# TramontanaPico.net
KiCad netlist of a schematic drawn in EAGLE
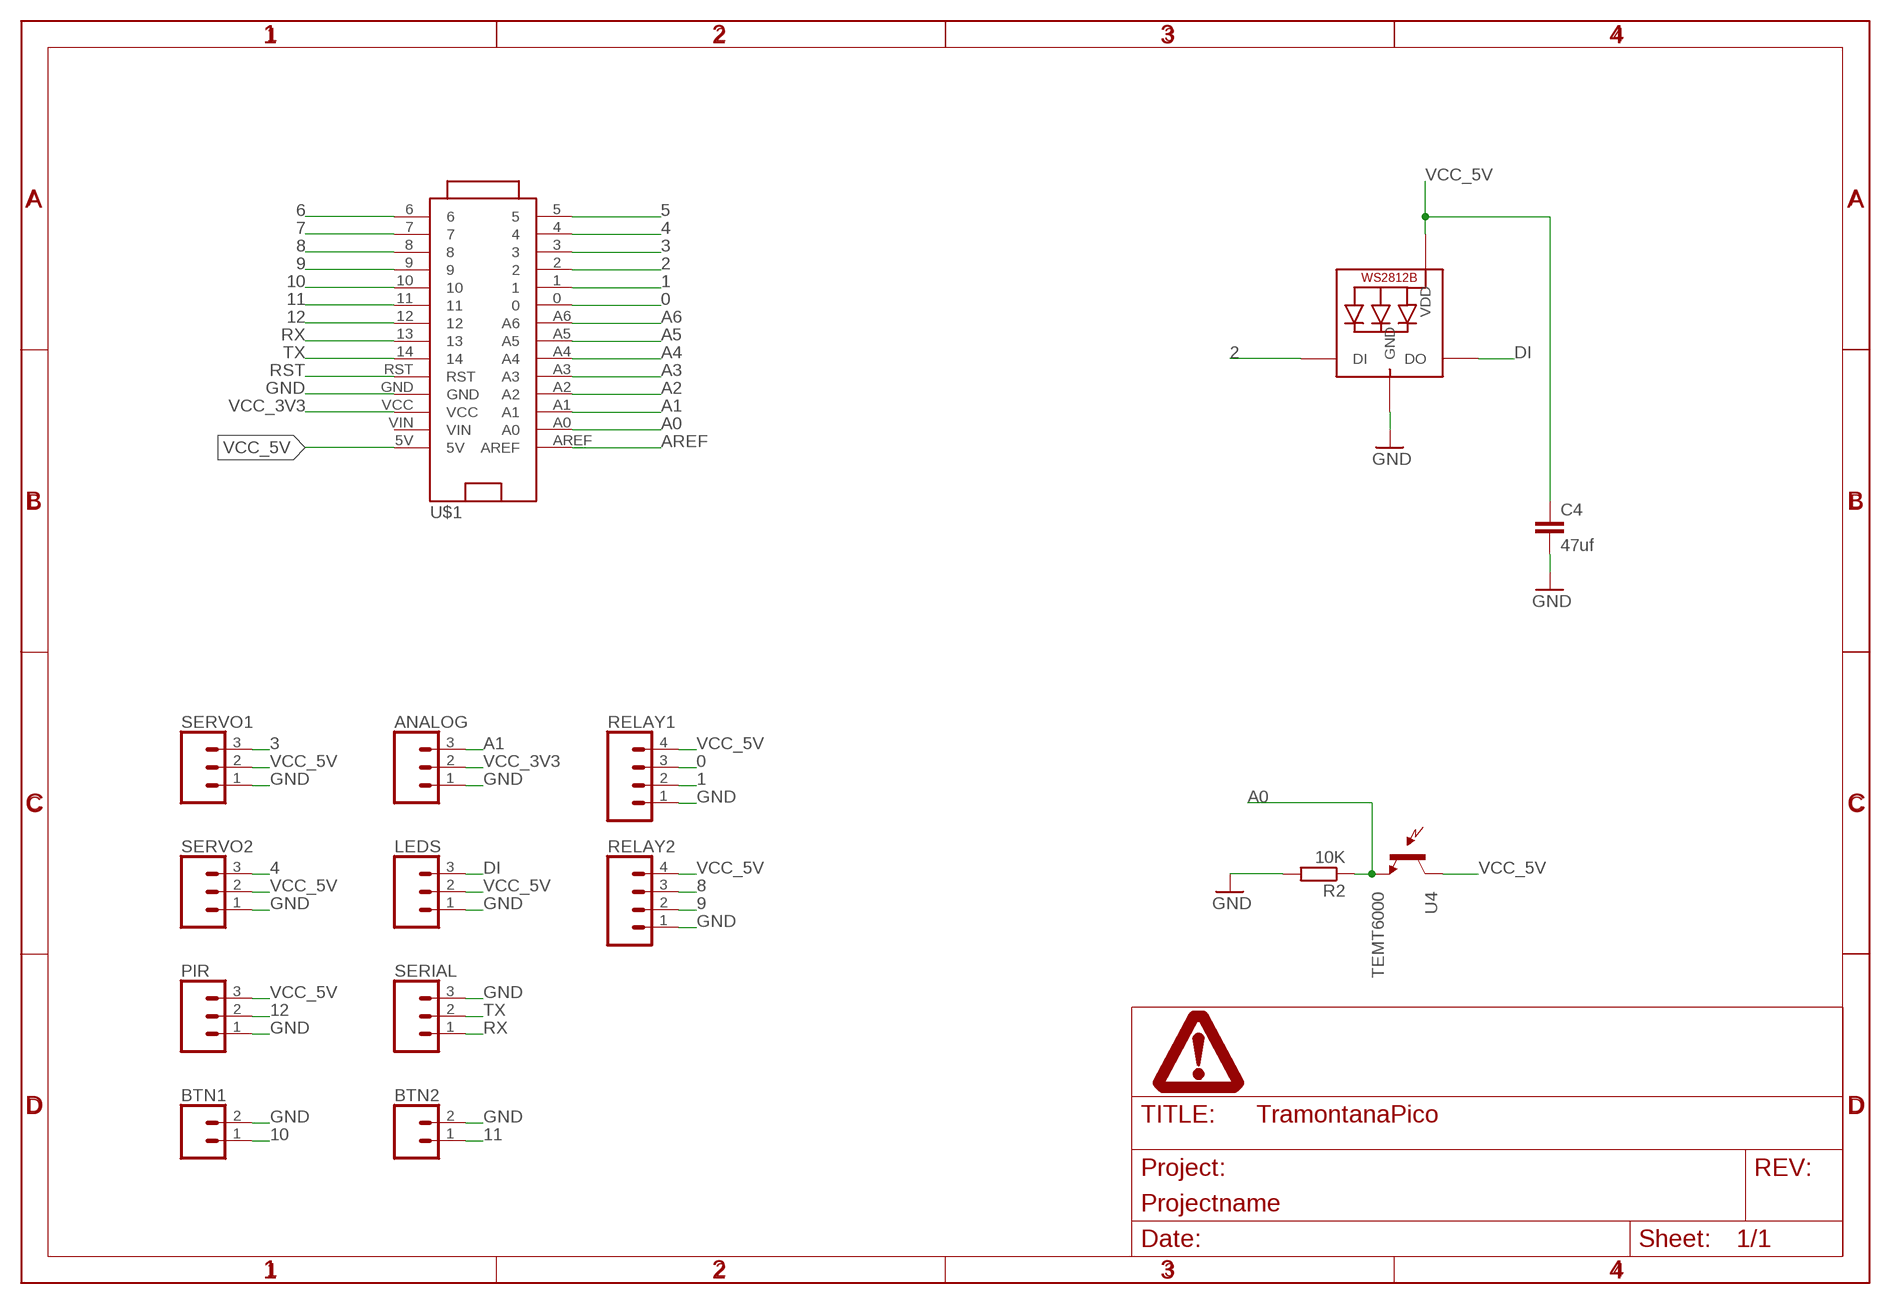
[diagram p0: schematic, sheet 1]

(export (version "E")
  (design (tool "Eeschema 10.0.6"))
  (components
    (comp (ref "ANALOG")
      (value "CONN_03LOCK")
      (footprint "eagle-import:1X03_LOCK")
      (libsource (lib "eagle-import") (part "CONN_03LOCK"))
    )
    (comp (ref "BTN1")
      (value "CONN_02LOCK")
      (footprint "eagle-import:1X02_LOCK")
      (libsource (lib "eagle-import") (part "CONN_02LOCK"))
    )
    (comp (ref "BTN2")
      (value "CONN_02LOCK")
      (footprint "eagle-import:1X02_LOCK")
      (libsource (lib "eagle-import") (part "CONN_02LOCK"))
    )
    (comp (ref "C4")
      (value "47uf")
      (footprint "eagle-import:C0603")
      (libsource (lib "eagle-import") (part "C-EUC0603"))
    )
    (comp (ref "HTTP")
      (value "FRAME_DINA4_L")
      (footprint "eagle-import:DP_LOGO")
      (fields (field (name "PROJECT") "Projectname"))
      (libsource (lib "eagle-import") (part "FRAME_DINA4_L"))
    )
    (comp (ref "LED1")
      (value "WS2812B5050")
      (footprint "eagle-import:WS2812B")
      (libsource (lib "eagle-import") (part "WS2812B5050"))
    )
    (comp (ref "LEDS")
      (value "CONN_03LOCK")
      (footprint "eagle-import:1X03_LOCK")
      (libsource (lib "eagle-import") (part "CONN_03LOCK"))
    )
    (comp (ref "PIR")
      (value "CONN_03LOCK")
      (footprint "eagle-import:1X03_LOCK")
      (libsource (lib "eagle-import") (part "CONN_03LOCK"))
    )
    (comp (ref "R2")
      (value "10K")
      (footprint "eagle-import:R0603")
      (libsource (lib "eagle-import") (part "R-EU_R0603"))
    )
    (comp (ref "RELAY1")
      (value "CONN_04LOCK")
      (footprint "eagle-import:1X04_LOCK")
      (libsource (lib "eagle-import") (part "CONN_04LOCK"))
    )
    (comp (ref "RELAY2")
      (value "CONN_04LOCK")
      (footprint "eagle-import:1X04_LOCK")
      (libsource (lib "eagle-import") (part "CONN_04LOCK"))
    )
    (comp (ref "SERIAL")
      (value "CONN_03LOCK")
      (footprint "eagle-import:1X03_LOCK")
      (libsource (lib "eagle-import") (part "CONN_03LOCK"))
    )
    (comp (ref "SERVO1")
      (value "CONN_03LOCK")
      (footprint "eagle-import:1X03_LOCK")
      (libsource (lib "eagle-import") (part "CONN_03LOCK"))
    )
    (comp (ref "SERVO2")
      (value "CONN_03LOCK")
      (footprint "eagle-import:1X03_LOCK")
      (libsource (lib "eagle-import") (part "CONN_03LOCK"))
    )
    (comp (ref "U$1")
      (value "MKR1000")
      (footprint "eagle-import:MKR1000")
      (libsource (lib "eagle-import") (part "MKR1000"))
    )
    (comp (ref "U4")
      (value "TEMT6000")
      (footprint "eagle-import:TEMT6000-SEN")
      (libsource (lib "eagle-import") (part "TEMT6000"))
    )
  )
  (nets
    (net (code "1") (name "/0") (class "Default")
      (node (ref "RELAY1") (pin "3") (pinfunction "3_3") (pintype "passive"))
      (node (ref "U$1") (pin "0") (pinfunction "0_0") (pintype "bidirectional"))
    )
    (net (code "2") (name "/1") (class "Default")
      (node (ref "RELAY1") (pin "2") (pinfunction "2_2") (pintype "passive"))
      (node (ref "U$1") (pin "1") (pinfunction "1_1") (pintype "bidirectional"))
    )
    (net (code "3") (name "/2") (class "Default")
      (node (ref "LED1") (pin "4-DIN") (pinfunction "DI_4-DIN") (pintype "input"))
      (node (ref "U$1") (pin "2") (pinfunction "2_2") (pintype "bidirectional"))
    )
    (net (code "4") (name "/3") (class "Default")
      (node (ref "SERVO1") (pin "3") (pinfunction "3_3") (pintype "passive"))
      (node (ref "U$1") (pin "3") (pinfunction "3_3") (pintype "bidirectional"))
    )
    (net (code "5") (name "/4") (class "Default")
      (node (ref "SERVO2") (pin "3") (pinfunction "3_3") (pintype "passive"))
      (node (ref "U$1") (pin "4") (pinfunction "4_4") (pintype "bidirectional"))
    )
    (net (code "6") (name "/5") (class "Default")
      (node (ref "U$1") (pin "5") (pinfunction "5_5") (pintype "bidirectional"))
    )
    (net (code "7") (name "/6") (class "Default")
      (node (ref "U$1") (pin "6") (pinfunction "6_6") (pintype "bidirectional"))
    )
    (net (code "8") (name "/7") (class "Default")
      (node (ref "U$1") (pin "7") (pinfunction "7_7") (pintype "bidirectional"))
    )
    (net (code "9") (name "/8") (class "Default")
      (node (ref "RELAY2") (pin "3") (pinfunction "3_3") (pintype "passive"))
      (node (ref "U$1") (pin "8") (pinfunction "8_8") (pintype "bidirectional"))
    )
    (net (code "10") (name "/9") (class "Default")
      (node (ref "RELAY2") (pin "2") (pinfunction "2_2") (pintype "passive"))
      (node (ref "U$1") (pin "9") (pinfunction "9_9") (pintype "bidirectional"))
    )
    (net (code "11") (name "/10") (class "Default")
      (node (ref "BTN1") (pin "1") (pinfunction "1_1") (pintype "passive"))
      (node (ref "U$1") (pin "10") (pinfunction "10_10") (pintype "bidirectional"))
    )
    (net (code "12") (name "/11") (class "Default")
      (node (ref "BTN2") (pin "1") (pinfunction "1_1") (pintype "passive"))
      (node (ref "U$1") (pin "11") (pinfunction "11_11") (pintype "bidirectional"))
    )
    (net (code "13") (name "/12") (class "Default")
      (node (ref "PIR") (pin "2") (pinfunction "2_2") (pintype "passive"))
      (node (ref "U$1") (pin "12") (pinfunction "12_12") (pintype "bidirectional"))
    )
    (net (code "14") (name "/A0") (class "Default")
      (node (ref "R2") (pin "1") (pinfunction "1_1") (pintype "passive"))
      (node (ref "U$1") (pin "A0") (pinfunction "A0_A0") (pintype "bidirectional"))
      (node (ref "U4") (pin "EMITTER") (pinfunction "E1_EMITTER") (pintype "passive"))
    )
    (net (code "15") (name "/A1") (class "Default")
      (node (ref "ANALOG") (pin "3") (pinfunction "3_3") (pintype "passive"))
      (node (ref "U$1") (pin "A1") (pinfunction "A1_A1") (pintype "bidirectional"))
    )
    (net (code "16") (name "/A2") (class "Default")
      (node (ref "U$1") (pin "A2") (pinfunction "A2_A2") (pintype "bidirectional"))
    )
    (net (code "17") (name "/A3") (class "Default")
      (node (ref "U$1") (pin "A3") (pinfunction "A3_A3") (pintype "bidirectional"))
    )
    (net (code "18") (name "/A4") (class "Default")
      (node (ref "U$1") (pin "A4") (pinfunction "A4_A4") (pintype "bidirectional"))
    )
    (net (code "19") (name "/A5") (class "Default")
      (node (ref "U$1") (pin "A5") (pinfunction "A5_A5") (pintype "bidirectional"))
    )
    (net (code "20") (name "/A6") (class "Default")
      (node (ref "U$1") (pin "A6") (pinfunction "A6_A6") (pintype "bidirectional"))
    )
    (net (code "21") (name "/AREF") (class "Default")
      (node (ref "U$1") (pin "AREF") (pinfunction "AREF_AREF") (pintype "bidirectional"))
    )
    (net (code "22") (name "/DI") (class "Default")
      (node (ref "LED1") (pin "2-DOUT") (pinfunction "DO_2-DOUT") (pintype "output"))
      (node (ref "LEDS") (pin "3") (pinfunction "3_3") (pintype "passive"))
    )
    (net (code "23") (name "/RST") (class "Default")
      (node (ref "U$1") (pin "RST") (pinfunction "RST_RST") (pintype "bidirectional"))
    )
    (net (code "24") (name "/RX") (class "Default")
      (node (ref "SERIAL") (pin "1") (pinfunction "1_1") (pintype "passive"))
      (node (ref "U$1") (pin "13") (pinfunction "13_13") (pintype "bidirectional"))
    )
    (net (code "25") (name "/TX") (class "Default")
      (node (ref "SERIAL") (pin "2") (pinfunction "2_2") (pintype "passive"))
      (node (ref "U$1") (pin "14") (pinfunction "14_14") (pintype "bidirectional"))
    )
    (net (code "26") (name "/VCC_3V3") (class "Default")
      (node (ref "ANALOG") (pin "2") (pinfunction "2_2") (pintype "passive"))
      (node (ref "U$1") (pin "VCC") (pinfunction "VCC_VCC") (pintype "bidirectional"))
    )
    (net (code "27") (name "GND") (class "Default")
      (node (ref "ANALOG") (pin "1") (pinfunction "1_1") (pintype "passive"))
      (node (ref "BTN1") (pin "2") (pinfunction "2_2") (pintype "passive"))
      (node (ref "BTN2") (pin "2") (pinfunction "2_2") (pintype "passive"))
      (node (ref "C4") (pin "2") (pinfunction "2_2") (pintype "passive"))
      (node (ref "LED1") (pin "3-GND") (pinfunction "GND_3-GND") (pintype "power_in"))
      (node (ref "LEDS") (pin "1") (pinfunction "1_1") (pintype "passive"))
      (node (ref "PIR") (pin "1") (pinfunction "1_1") (pintype "passive"))
      (node (ref "R2") (pin "2") (pinfunction "2_2") (pintype "passive"))
      (node (ref "RELAY1") (pin "1") (pinfunction "1_1") (pintype "passive"))
      (node (ref "RELAY2") (pin "1") (pinfunction "1_1") (pintype "passive"))
      (node (ref "SERIAL") (pin "3") (pinfunction "3_3") (pintype "passive"))
      (node (ref "SERVO1") (pin "1") (pinfunction "1_1") (pintype "passive"))
      (node (ref "SERVO2") (pin "1") (pinfunction "1_1") (pintype "passive"))
      (node (ref "U$1") (pin "GND") (pinfunction "GND_GND") (pintype "bidirectional"))
    )
    (net (code "28") (name "VCC_5V") (class "Default")
      (node (ref "C4") (pin "1") (pinfunction "1_1") (pintype "passive"))
      (node (ref "LED1") (pin "1-VDD") (pinfunction "VDD_1-VDD") (pintype "power_in"))
      (node (ref "LEDS") (pin "2") (pinfunction "2_2") (pintype "passive"))
      (node (ref "PIR") (pin "3") (pinfunction "3_3") (pintype "passive"))
      (node (ref "RELAY1") (pin "4") (pinfunction "4_4") (pintype "passive"))
      (node (ref "RELAY2") (pin "4") (pinfunction "4_4") (pintype "passive"))
      (node (ref "SERVO1") (pin "2") (pinfunction "2_2") (pintype "passive"))
      (node (ref "SERVO2") (pin "2") (pinfunction "2_2") (pintype "passive"))
      (node (ref "U$1") (pin "5V") (pinfunction "5V_5V") (pintype "bidirectional"))
      (node (ref "U4") (pin "COLLECTOR") (pinfunction "C1_COLLECTOR") (pintype "passive"))
    )
    (net (code "29") (name "unconnected-(U$1-PadVIN)") (class "Default")
      (node (ref "U$1") (pin "VIN") (pinfunction "VIN_VIN") (pintype "bidirectional"))
    )
  )
)
